# MCU.net
KiCad netlist of a schematic drawn in Altium Designer
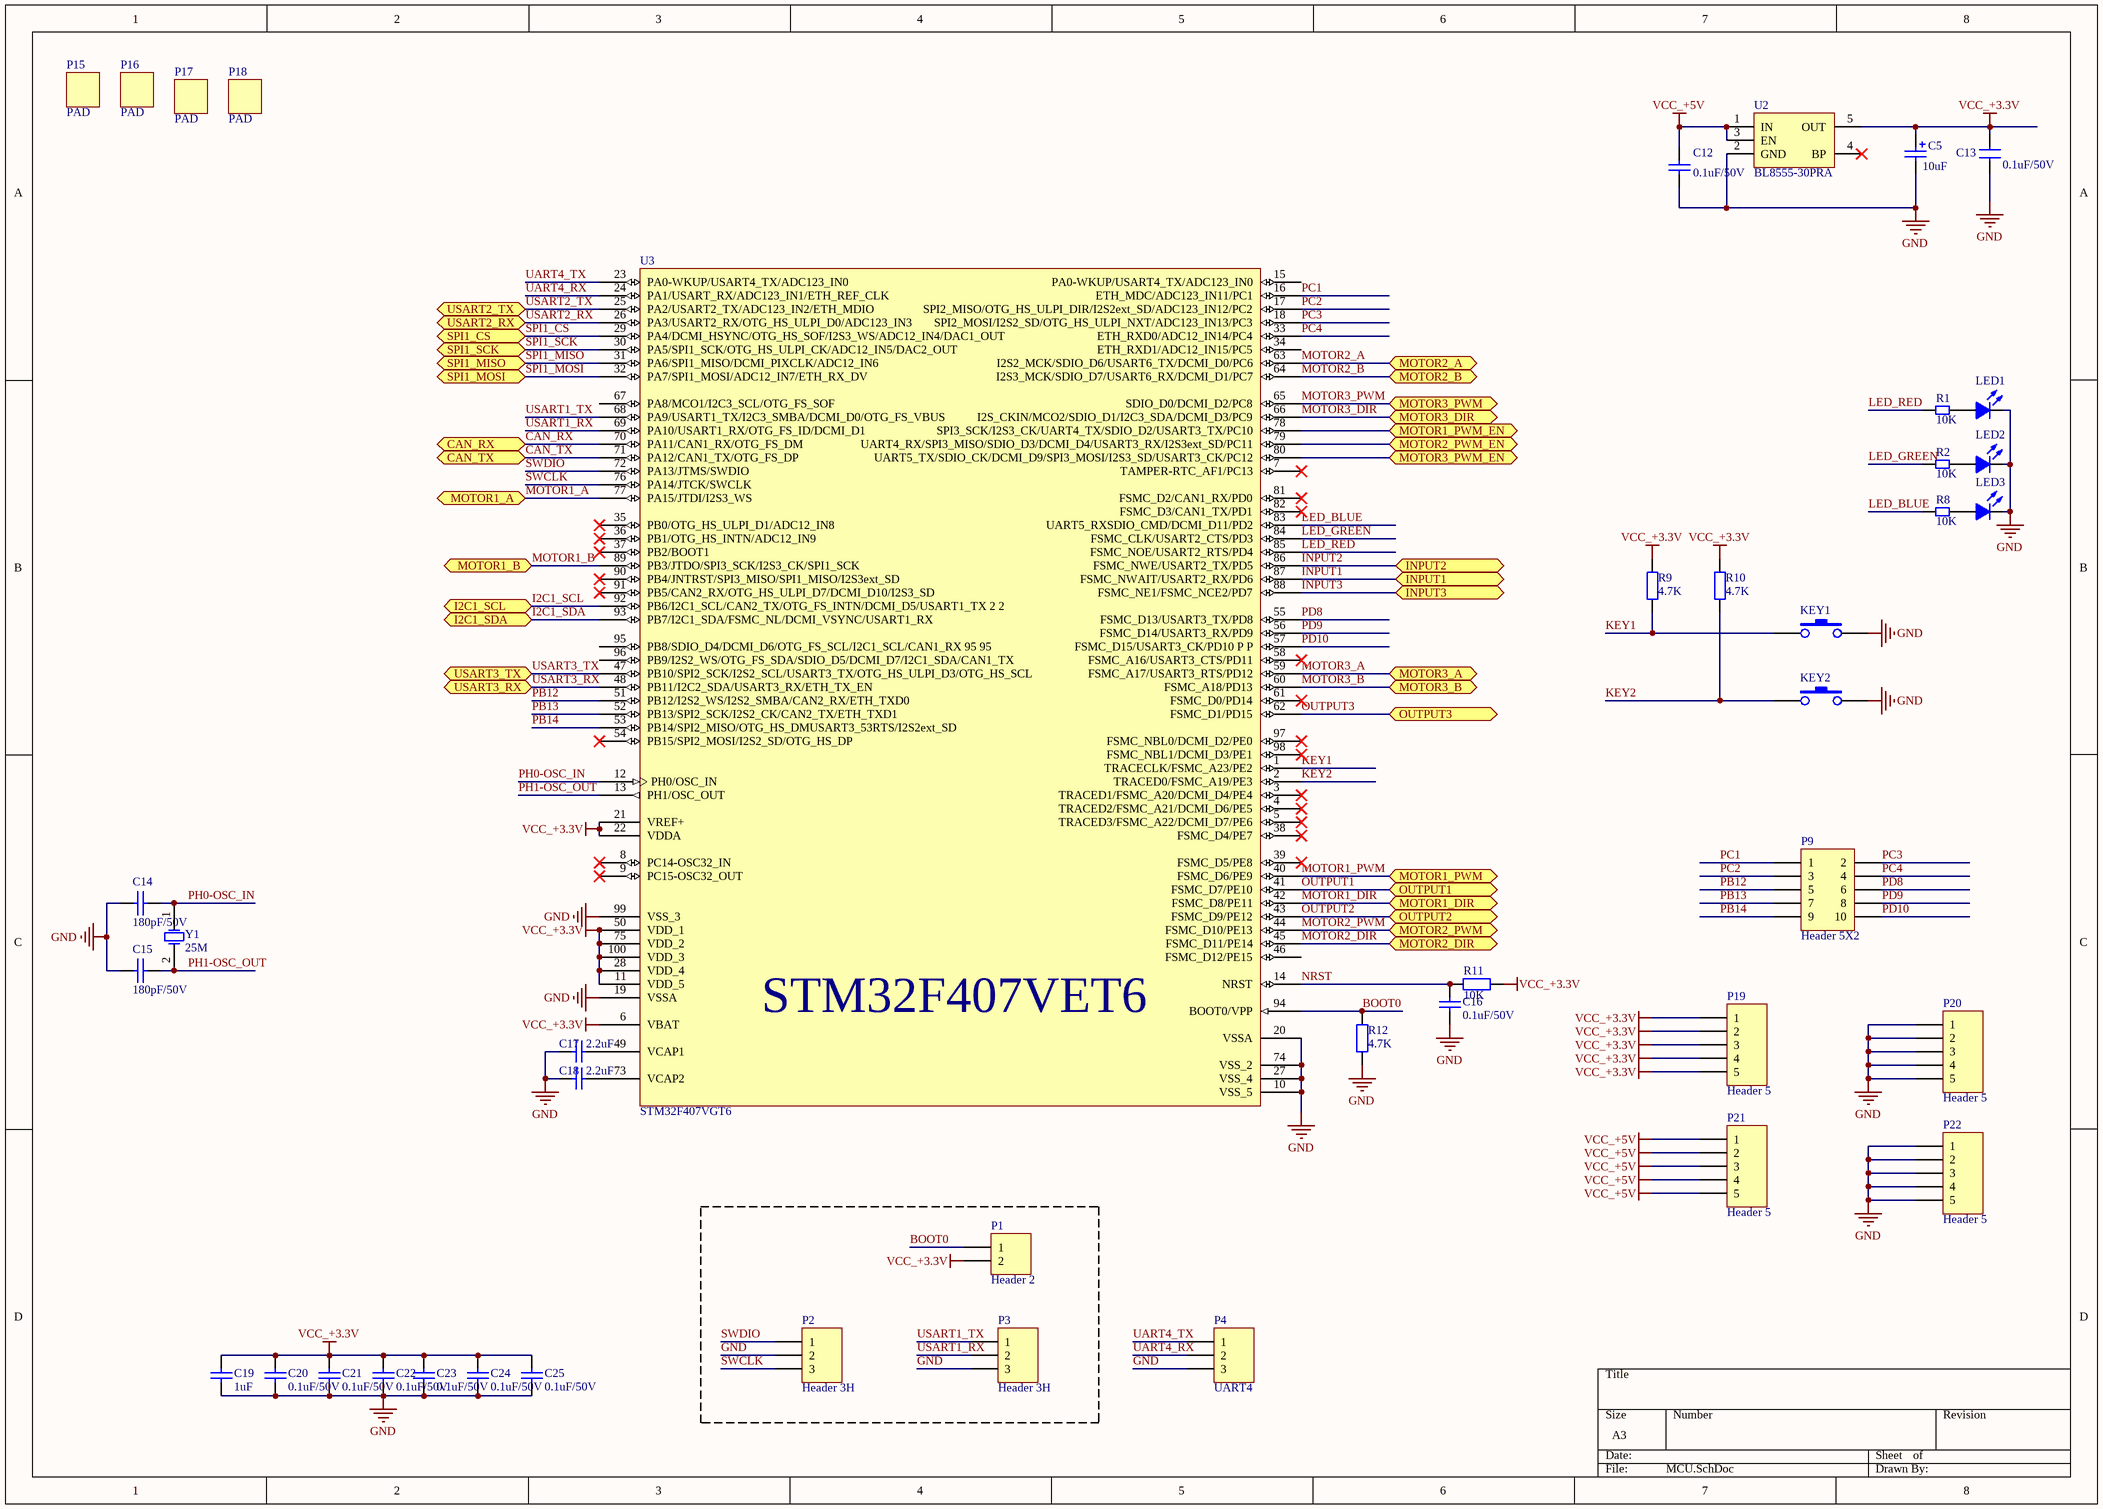
[diagram p0: MCU.SchDoc]

(export (version "E")
  (design (tool "Eeschema 10.0.6"))
  (components
    (comp (ref "C5")
      (value "10uF")
      (footprint "CAPTANC")
      (description "Polarized Capacitor (Radial)")
      (fields (field (name "PUBLISHER") "Altium Limited"))
      (libsource (lib "Calf") (part "Cap Pol"))
    )
    (comp (ref "C12")
      (value "0.1uF/50V")
      (footprint "0603C")
      (description "Capacitor")
      (fields (field (name "PUBLISHER") "Altium Limited"))
      (libsource (lib "Calf") (part "Cap"))
    )
    (comp (ref "C13") (value "0.1uF/50V") (footprint "0603C") (libsource (lib "0603C") (part "CAP")))
    (comp (ref "C14") (value "180pF/50V") (footprint "0603C") (libsource (lib "*") (part "0603C")))
    (comp (ref "C15") (value "180pF/50V") (footprint "0603C") (libsource (lib "*") (part "0603C")))
    (comp (ref "C16")
      (value "0.1uF/50V")
      (footprint "0603C")
      (description "Capacitor")
      (fields (field (name "PUBLISHER") "Altium Limited"))
      (libsource (lib "Calf") (part "Cap"))
    )
    (comp (ref "C17")
      (value "2.2uF")
      (footprint "0603C")
      (description "Capacitor")
      (fields (field (name "PUBLISHER") "Altium Limited"))
      (libsource (lib "Calf") (part "Cap"))
    )
    (comp (ref "C18")
      (value "2.2uF")
      (footprint "0603C")
      (description "Capacitor")
      (fields (field (name "PUBLISHER") "Altium Limited"))
      (libsource (lib "Calf") (part "Cap"))
    )
    (comp (ref "C19")
      (value "1uF")
      (footprint "0603C")
      (description "Capacitor")
      (fields (field (name "PUBLISHER") "Altium Limited"))
      (libsource (lib "Calf") (part "Cap"))
    )
    (comp (ref "C20")
      (value "0.1uF/50V")
      (footprint "0603C")
      (description "Capacitor")
      (fields (field (name "PUBLISHER") "Altium Limited"))
      (libsource (lib "Calf") (part "Cap"))
    )
    (comp (ref "C21")
      (value "0.1uF/50V")
      (footprint "0603C")
      (description "Capacitor")
      (fields (field (name "PUBLISHER") "Altium Limited"))
      (libsource (lib "Calf") (part "Cap"))
    )
    (comp (ref "C22")
      (value "0.1uF/50V")
      (footprint "0603C")
      (description "Capacitor")
      (fields (field (name "PUBLISHER") "Altium Limited"))
      (libsource (lib "Calf") (part "Cap"))
    )
    (comp (ref "C23")
      (value "0.1uF/50V")
      (footprint "0603C")
      (description "Capacitor")
      (fields (field (name "PUBLISHER") "Altium Limited"))
      (libsource (lib "Calf") (part "Cap"))
    )
    (comp (ref "C24")
      (value "0.1uF/50V")
      (footprint "0603C")
      (description "Capacitor")
      (fields (field (name "PUBLISHER") "Altium Limited"))
      (libsource (lib "Calf") (part "Cap"))
    )
    (comp (ref "C25")
      (value "0.1uF/50V")
      (footprint "0603C")
      (description "Capacitor")
      (fields (field (name "PUBLISHER") "Altium Limited"))
      (libsource (lib "Calf") (part "Cap"))
    )
    (comp (ref "KEY1") (value "~") (footprint "KEY_SMT") (libsource (lib "stmDL") (part "SW-PB")))
    (comp (ref "KEY2") (value "~") (footprint "KEY_SMT") (libsource (lib "stmDL") (part "SW-PB")))
    (comp (ref "LED1")
      (value "LED")
      (footprint "LED-0603")
      (description "Typical INFRARED GaAs LED")
      (fields (field (name "PUBLISHER") "Altium Limited"))
      (libsource (lib "Calf") (part "LED"))
    )
    (comp (ref "LED2")
      (value "LED")
      (footprint "LED-0603")
      (description "Typical INFRARED GaAs LED")
      (fields (field (name "PUBLISHER") "Altium Limited"))
      (libsource (lib "Calf") (part "LED"))
    )
    (comp (ref "LED3")
      (value "LED")
      (footprint "LED-0603")
      (description "Typical INFRARED GaAs LED")
      (fields (field (name "PUBLISHER") "Altium Limited"))
      (libsource (lib "Calf") (part "LED"))
    )
    (comp (ref "P1")
      (value "Header 2")
      (footprint "HDR1*2")
      (description "Header, 2-Pin")
      (fields (field (name "PUBLISHER") "Altium Limited"))
      (libsource (lib "Miscellaneous Connectors") (part "Header 2"))
    )
    (comp (ref "P2")
      (value "Header 3H")
      (footprint "XH254-3P")
      (description "Header, 3-Pin, Right Angle")
      (fields (field (name "PUBLISHER") "Altium Limited"))
      (libsource (lib "Miscellaneous Connectors") (part "Header 3H"))
    )
    (comp (ref "P3")
      (value "Header 3H")
      (footprint "XH254-3P")
      (description "Header, 3-Pin, Right Angle")
      (fields (field (name "PUBLISHER") "Altium Limited"))
      (libsource (lib "Miscellaneous Connectors") (part "Header 3H"))
    )
    (comp (ref "P4")
      (value "UART4")
      (footprint "XH254-3P")
      (description "Header, 3-Pin, Right Angle")
      (fields (field (name "PUBLISHER") "Altium Limited"))
      (libsource (lib "Miscellaneous Connectors") (part "Header 3H"))
    )
    (comp (ref "P9")
      (value "Header 5X2")
      (footprint "HDR2X5")
      (description "Header, 5-Pin, Dual row")
      (fields (field (name "PUBLISHER") "Altium Limited"))
      (libsource (lib "Miscellaneous Connectors") (part "Header 5X2"))
    )
    (comp (ref "P15") (value "PAD") (footprint "PAD 3mm") (libsource (lib "Schlib") (part "PAD")))
    (comp (ref "P16") (value "PAD") (footprint "PAD 3mm") (libsource (lib "Schlib") (part "PAD")))
    (comp (ref "P17") (value "PAD") (footprint "PAD 3mm") (libsource (lib "Schlib") (part "PAD")))
    (comp (ref "P18") (value "PAD") (footprint "PAD 3mm") (libsource (lib "Schlib") (part "PAD")))
    (comp (ref "P19")
      (value "Header 5")
      (footprint "HDR1X5")
      (description "Header, 5-Pin")
      (fields (field (name "PUBLISHER") "Altium Limited"))
      (libsource (lib "Miscellaneous Connectors") (part "Header 5"))
    )
    (comp (ref "P20")
      (value "Header 5")
      (footprint "HDR1X5")
      (description "Header, 5-Pin")
      (fields (field (name "PUBLISHER") "Altium Limited"))
      (libsource (lib "Miscellaneous Connectors") (part "Header 5"))
    )
    (comp (ref "P21")
      (value "Header 5")
      (footprint "HDR1X5")
      (description "Header, 5-Pin")
      (fields (field (name "PUBLISHER") "Altium Limited"))
      (libsource (lib "Miscellaneous Connectors") (part "Header 5"))
    )
    (comp (ref "P22")
      (value "Header 5")
      (footprint "HDR1X5")
      (description "Header, 5-Pin")
      (fields (field (name "PUBLISHER") "Altium Limited"))
      (libsource (lib "Miscellaneous Connectors") (part "Header 5"))
    )
    (comp (ref "R1")
      (value "10K")
      (footprint "0603R")
      (description "Resistor")
      (fields (field (name "PUBLISHER") "Altium Limited"))
      (libsource (lib "Calf") (part "Res2"))
    )
    (comp (ref "R2")
      (value "10K")
      (footprint "0603R")
      (description "Resistor")
      (fields (field (name "PUBLISHER") "Altium Limited"))
      (libsource (lib "Calf") (part "Res2"))
    )
    (comp (ref "R8")
      (value "10K")
      (footprint "0603R")
      (description "Resistor")
      (fields (field (name "PUBLISHER") "Altium Limited"))
      (libsource (lib "Calf") (part "Res2"))
    )
    (comp (ref "R9") (value "4.7K") (footprint "0603R") (libsource (lib "*") (part "0603R")))
    (comp (ref "R10") (value "4.7K") (footprint "0603R") (libsource (lib "*") (part "0603R")))
    (comp (ref "R11") (value "10K") (footprint "0603R") (libsource (lib "") (part "0603R_2")))
    (comp (ref "R12") (value "4.7K") (footprint "0603R") (libsource (lib "") (part "0603R_1")))
    (comp (ref "U2") (value "BL8555-30PRA") (footprint "SOT23-5") (libsource (lib "Calf") (part "SGM2019")))
    (comp (ref "U3")
      (value "STM32F407VGT6")
      (footprint "LQFP-100_14x14x05P")
      (libsource (lib "STM32F407VGT6") (part "STM32F407VGT6"))
    )
    (comp (ref "Y1")
      (value "25M")
      (footprint "XTAL")
      (description "Crystal Oscillator")
      (fields (field (name "PUBLISHER") "Altium Limited"))
      (libsource (lib "*") (part "XTAL"))
    )
  )
  (nets
    (net (code "1") (name "/BOOT0") (class "Default")
      (node (ref "P1") (pin "1") (pinfunction "1_1") (pintype "passive"))
      (node (ref "R12") (pin "2") (pinfunction "2_2") (pintype "passive"))
      (node (ref "U3") (pin "94") (pinfunction "BOOT0/VPP_94") (pintype "input"))
    )
    (net (code "2") (name "/CAN_RX") (class "Default")
      (node (ref "U3") (pin "70") (pinfunction "PA11/CAN1_RX/OTG_FS_DM_70") (pintype "bidirectional"))
    )
    (net (code "3") (name "/CAN_TX") (class "Default")
      (node (ref "U3") (pin "71") (pinfunction "PA12/CAN1_TX/OTG_FS_DP_71") (pintype "bidirectional"))
    )
    (net (code "4") (name "/I2C1_SCL") (class "Default")
      (node (ref "U3") (pin "92") (pinfunction "PB6/I2C1_SCL/CAN2_TX/OTG_FS_INTN/DCMI_D5/USART1_TX_2_2_92") (pintype "bidirectional"))
    )
    (net (code "5") (name "/I2C1_SDA") (class "Default")
      (node (ref "U3") (pin "93") (pinfunction "PB7/I2C1_SDA/FSMC_NL/DCMI_VSYNC/USART1_RX_93") (pintype "bidirectional"))
    )
    (net (code "6") (name "/INPUT1") (class "Default")
      (node (ref "U3") (pin "87") (pinfunction "FSMC_NWAIT/USART2_RX/PD6_87") (pintype "bidirectional"))
    )
    (net (code "7") (name "/INPUT2") (class "Default")
      (node (ref "U3") (pin "86") (pinfunction "FSMC_NWE/USART2_TX/PD5_86") (pintype "bidirectional"))
    )
    (net (code "8") (name "/INPUT3") (class "Default")
      (node (ref "U3") (pin "88") (pinfunction "FSMC_NE1/FSMC_NCE2/PD7_88") (pintype "bidirectional"))
    )
    (net (code "9") (name "/KEY1") (class "Default")
      (node (ref "KEY1") (pin "1") (pinfunction "1_1") (pintype "passive"))
      (node (ref "R9") (pin "2") (pinfunction "2_2") (pintype "passive"))
      (node (ref "U3") (pin "1") (pinfunction "TRACECLK/FSMC_A23/PE2_1") (pintype "bidirectional"))
    )
    (net (code "10") (name "/KEY2") (class "Default")
      (node (ref "KEY2") (pin "1") (pinfunction "1_1") (pintype "passive"))
      (node (ref "R10") (pin "2") (pinfunction "2_2") (pintype "passive"))
      (node (ref "U3") (pin "2") (pinfunction "TRACED0/FSMC_A19/PE3_2") (pintype "bidirectional"))
    )
    (net (code "11") (name "/LED_BLUE") (class "Default")
      (node (ref "R8") (pin "1") (pinfunction "1_1") (pintype "passive"))
      (node (ref "U3") (pin "83") (pinfunction "UART5_RXSDIO_CMD/DCMI_D11/PD2_83") (pintype "bidirectional"))
    )
    (net (code "12") (name "/LED_GREEN") (class "Default")
      (node (ref "R2") (pin "1") (pinfunction "1_1") (pintype "passive"))
      (node (ref "U3") (pin "84") (pinfunction "FSMC_CLK/USART2_CTS/PD3_84") (pintype "bidirectional"))
    )
    (net (code "13") (name "/LED_RED") (class "Default")
      (node (ref "R1") (pin "1") (pinfunction "1_1") (pintype "passive"))
      (node (ref "U3") (pin "85") (pinfunction "FSMC_NOE/USART2_RTS/PD4_85") (pintype "bidirectional"))
    )
    (net (code "14") (name "/MOTOR1_A") (class "Default")
      (node (ref "U3") (pin "77") (pinfunction "PA15/JTDI/I2S3_WS_77") (pintype "bidirectional"))
    )
    (net (code "15") (name "/MOTOR1_B") (class "Default")
      (node (ref "U3") (pin "89") (pinfunction "PB3/JTDO/SPI3_SCK/I2S3_CK/SPI1_SCK_89") (pintype "bidirectional"))
    )
    (net (code "16") (name "/MOTOR1_DIR") (class "Default")
      (node (ref "U3") (pin "42") (pinfunction "FSMC_D8/PE11_42") (pintype "bidirectional"))
    )
    (net (code "17") (name "/MOTOR1_PWM") (class "Default")
      (node (ref "U3") (pin "40") (pinfunction "FSMC_D6/PE9_40") (pintype "bidirectional"))
    )
    (net (code "18") (name "/MOTOR1_PWM_EN") (class "Default")
      (node (ref "U3") (pin "78") (pinfunction "SPI3_SCK/I2S3_CK/UART4_TX/SDIO_D2/USART3_TX/PC10_78") (pintype "bidirectional"))
    )
    (net (code "19") (name "/MOTOR2_A") (class "Default")
      (node (ref "U3") (pin "63") (pinfunction "I2S2_MCK/SDIO_D6/USART6_TX/DCMI_D0/PC6_63") (pintype "bidirectional"))
    )
    (net (code "20") (name "/MOTOR2_B") (class "Default")
      (node (ref "U3") (pin "64") (pinfunction "I2S3_MCK/SDIO_D7/USART6_RX/DCMI_D1/PC7_64") (pintype "bidirectional"))
    )
    (net (code "21") (name "/MOTOR2_DIR") (class "Default")
      (node (ref "U3") (pin "45") (pinfunction "FSMC_D11/PE14_45") (pintype "bidirectional"))
    )
    (net (code "22") (name "/MOTOR2_PWM") (class "Default")
      (node (ref "U3") (pin "44") (pinfunction "FSMC_D10/PE13_44") (pintype "bidirectional"))
    )
    (net (code "23") (name "/MOTOR2_PWM_EN") (class "Default")
      (node (ref "U3") (pin "79") (pinfunction "UART4_RX/SPI3_MISO/SDIO_D3/DCMI_D4/USART3_RX/I2S3ext_SD/PC11_79") (pintype "bidirectional"))
    )
    (net (code "24") (name "/MOTOR3_A") (class "Default")
      (node (ref "U3") (pin "59") (pinfunction "FSMC_A17/USART3_RTS/PD12_59") (pintype "bidirectional"))
    )
    (net (code "25") (name "/MOTOR3_B") (class "Default")
      (node (ref "U3") (pin "60") (pinfunction "FSMC_A18/PD13_60") (pintype "bidirectional"))
    )
    (net (code "26") (name "/MOTOR3_DIR") (class "Default")
      (node (ref "U3") (pin "66") (pinfunction "I2S_CKIN/MCO2/SDIO_D1/I2C3_SDA/DCMI_D3/PC9_66") (pintype "bidirectional"))
    )
    (net (code "27") (name "/MOTOR3_PWM") (class "Default")
      (node (ref "U3") (pin "65") (pinfunction "SDIO_D0/DCMI_D2/PC8_65") (pintype "bidirectional"))
    )
    (net (code "28") (name "/MOTOR3_PWM_EN") (class "Default")
      (node (ref "U3") (pin "80") (pinfunction "UART5_TX/SDIO_CK/DCMI_D9/SPI3_MOSI/I2S3_SD/USART3_CK/PC12_80") (pintype "bidirectional"))
    )
    (net (code "29") (name "/NRST") (class "Default")
      (node (ref "C16") (pin "2") (pinfunction "2_2") (pintype "passive"))
      (node (ref "R11") (pin "2") (pinfunction "2_2") (pintype "passive"))
      (node (ref "U3") (pin "14") (pinfunction "NRST_14") (pintype "bidirectional"))
    )
    (net (code "30") (name "/OUTPUT1") (class "Default")
      (node (ref "U3") (pin "41") (pinfunction "FSMC_D7/PE10_41") (pintype "bidirectional"))
    )
    (net (code "31") (name "/OUTPUT2") (class "Default")
      (node (ref "U3") (pin "43") (pinfunction "FSMC_D9/PE12_43") (pintype "bidirectional"))
    )
    (net (code "32") (name "/OUTPUT3") (class "Default")
      (node (ref "U3") (pin "62") (pinfunction "FSMC_D1/PD15_62") (pintype "bidirectional"))
    )
    (net (code "33") (name "/PB12") (class "Default")
      (node (ref "P9") (pin "5") (pinfunction "5_5") (pintype "passive"))
      (node (ref "U3") (pin "51") (pinfunction "PB12/I2S2_WS/I2S2_SMBA/CAN2_RX/ETH_TXD0_51") (pintype "bidirectional"))
    )
    (net (code "34") (name "/PB13") (class "Default")
      (node (ref "P9") (pin "7") (pinfunction "7_7") (pintype "passive"))
      (node (ref "U3") (pin "52") (pinfunction "PB13/SPI2_SCK/I2S2_CK/CAN2_TX/ETH_TXD1_52") (pintype "bidirectional"))
    )
    (net (code "35") (name "/PB14") (class "Default")
      (node (ref "P9") (pin "9") (pinfunction "9_9") (pintype "passive"))
      (node (ref "U3") (pin "53") (pinfunction "PB14/SPI2_MISO/OTG_HS_DMUSART3_53RTS/I2S2ext_SD_53") (pintype "bidirectional"))
    )
    (net (code "36") (name "/PC1") (class "Default")
      (node (ref "P9") (pin "1") (pinfunction "1_1") (pintype "passive"))
      (node (ref "U3") (pin "16") (pinfunction "ETH_MDC/ADC123_IN11/PC1_16") (pintype "bidirectional"))
    )
    (net (code "37") (name "/PC2") (class "Default")
      (node (ref "P9") (pin "3") (pinfunction "3_3") (pintype "passive"))
      (node (ref "U3") (pin "17") (pinfunction "SPI2_MISO/OTG_HS_ULPI_DIR/I2S2ext_SD/ADC123_IN12/PC2_17") (pintype "bidirectional"))
    )
    (net (code "38") (name "/PC3") (class "Default")
      (node (ref "P9") (pin "2") (pinfunction "2_2") (pintype "passive"))
      (node (ref "U3") (pin "18") (pinfunction "SPI2_MOSI/I2S2_SD/OTG_HS_ULPI_NXT/ADC123_IN13/PC3_18") (pintype "bidirectional"))
    )
    (net (code "39") (name "/PC4") (class "Default")
      (node (ref "P9") (pin "4") (pinfunction "4_4") (pintype "passive"))
      (node (ref "U3") (pin "33") (pinfunction "ETH_RXD0/ADC12_IN14/PC4_33") (pintype "bidirectional"))
    )
    (net (code "40") (name "/PD8") (class "Default")
      (node (ref "P9") (pin "6") (pinfunction "6_6") (pintype "passive"))
      (node (ref "U3") (pin "55") (pinfunction "FSMC_D13/USART3_TX/PD8_55") (pintype "bidirectional"))
    )
    (net (code "41") (name "/PD9") (class "Default")
      (node (ref "P9") (pin "8") (pinfunction "8_8") (pintype "passive"))
      (node (ref "U3") (pin "56") (pinfunction "FSMC_D14/USART3_RX/PD9_56") (pintype "bidirectional"))
    )
    (net (code "42") (name "/PD10") (class "Default")
      (node (ref "P9") (pin "10") (pinfunction "10_10") (pintype "passive"))
      (node (ref "U3") (pin "57") (pinfunction "FSMC_D15/USART3_CK/PD10_P_P_57") (pintype "bidirectional"))
    )
    (net (code "43") (name "/PH0-OSC_IN") (class "Default")
      (node (ref "C14") (pin "2") (pintype "passive"))
      (node (ref "U3") (pin "12") (pinfunction "PH0/OSC_IN_12") (pintype "input"))
      (node (ref "Y1") (pin "1") (pinfunction "OSC1_1") (pintype "passive"))
    )
    (net (code "44") (name "/PH1-OSC_OUT") (class "Default")
      (node (ref "C15") (pin "2") (pintype "passive"))
      (node (ref "U3") (pin "13") (pinfunction "PH1/OSC_OUT_13") (pintype "output"))
      (node (ref "Y1") (pin "2") (pinfunction "OSC2_2") (pintype "passive"))
    )
    (net (code "45") (name "/SPI1_CS") (class "Default")
      (node (ref "U3") (pin "29") (pinfunction "PA4/DCMI_HSYNC/OTG_HS_SOF/I2S3_WS/ADC12_IN4/DAC1_OUT_29") (pintype "bidirectional"))
    )
    (net (code "46") (name "/SPI1_MISO") (class "Default")
      (node (ref "U3") (pin "31") (pinfunction "PA6/SPI1_MISO/DCMI_PIXCLK/ADC12_IN6_31") (pintype "bidirectional"))
    )
    (net (code "47") (name "/SPI1_MOSI") (class "Default")
      (node (ref "U3") (pin "32") (pinfunction "PA7/SPI1_MOSI/ADC12_IN7/ETH_RX_DV_32") (pintype "bidirectional"))
    )
    (net (code "48") (name "/SPI1_SCK") (class "Default")
      (node (ref "U3") (pin "30") (pinfunction "PA5/SPI1_SCK/OTG_HS_ULPI_CK/ADC12_IN5/DAC2_OUT_30") (pintype "bidirectional"))
    )
    (net (code "49") (name "/SWCLK") (class "Default")
      (node (ref "P2") (pin "3") (pinfunction "3_3") (pintype "passive"))
      (node (ref "U3") (pin "76") (pinfunction "PA14/JTCK/SWCLK_76") (pintype "bidirectional"))
    )
    (net (code "50") (name "/SWDIO") (class "Default")
      (node (ref "P2") (pin "1") (pinfunction "1_1") (pintype "passive"))
      (node (ref "U3") (pin "72") (pinfunction "PA13/JTMS/SWDIO_72") (pintype "bidirectional"))
    )
    (net (code "51") (name "/UART4_RX") (class "Default")
      (node (ref "P4") (pin "2") (pinfunction "2_2") (pintype "passive"))
      (node (ref "U3") (pin "24") (pinfunction "PA1/USART_RX/ADC123_IN1/ETH_REF_CLK_24") (pintype "bidirectional"))
    )
    (net (code "52") (name "/UART4_TX") (class "Default")
      (node (ref "P4") (pin "1") (pinfunction "1_1") (pintype "passive"))
      (node (ref "U3") (pin "23") (pinfunction "PA0-WKUP/USART4_TX/ADC123_IN0_23") (pintype "bidirectional"))
    )
    (net (code "53") (name "/USART1_RX") (class "Default")
      (node (ref "P3") (pin "2") (pinfunction "2_2") (pintype "passive"))
      (node (ref "U3") (pin "69") (pinfunction "PA10/USART1_RX/OTG_FS_ID/DCMI_D1_69") (pintype "bidirectional"))
    )
    (net (code "54") (name "/USART1_TX") (class "Default")
      (node (ref "P3") (pin "1") (pinfunction "1_1") (pintype "passive"))
      (node (ref "U3") (pin "68") (pinfunction "PA9/USART1_TX/I2C3_SMBA/DCMI_D0/OTG_FS_VBUS_68") (pintype "bidirectional"))
    )
    (net (code "55") (name "/USART2_RX") (class "Default")
      (node (ref "U3") (pin "26") (pinfunction "PA3/USART2_RX/OTG_HS_ULPI_D0/ADC123_IN3_26") (pintype "bidirectional"))
    )
    (net (code "56") (name "/USART2_TX") (class "Default")
      (node (ref "U3") (pin "25") (pinfunction "PA2/USART2_TX/ADC123_IN2/ETH_MDIO_25") (pintype "bidirectional"))
    )
    (net (code "57") (name "/USART3_RX") (class "Default")
      (node (ref "U3") (pin "48") (pinfunction "PB11/I2C2_SDA/USART3_RX/ETH_TX_EN_48") (pintype "bidirectional"))
    )
    (net (code "58") (name "/USART3_TX") (class "Default")
      (node (ref "U3") (pin "47") (pinfunction "PB10/SPI2_SCK/I2S2_SCL/USART3_TX/OTG_HS_ULPI_D3/OTG_HS_SCL_47") (pintype "bidirectional"))
    )
    (net (code "59") (name "GND") (class "Default")
      (node (ref "C12") (pin "1") (pinfunction "1_1") (pintype "passive"))
      (node (ref "C13") (pin "2") (pinfunction "2_2") (pintype "passive"))
      (node (ref "C14") (pin "1") (pintype "passive"))
      (node (ref "C15") (pin "1") (pintype "passive"))
      (node (ref "C16") (pin "1") (pinfunction "1_1") (pintype "passive"))
      (node (ref "C17") (pin "2") (pinfunction "2_2") (pintype "passive"))
      (node (ref "C18") (pin "2") (pinfunction "2_2") (pintype "passive"))
      (node (ref "C19") (pin "1") (pinfunction "1_1") (pintype "passive"))
      (node (ref "C20") (pin "1") (pinfunction "1_1") (pintype "passive"))
      (node (ref "C21") (pin "1") (pinfunction "1_1") (pintype "passive"))
      (node (ref "C22") (pin "1") (pinfunction "1_1") (pintype "passive"))
      (node (ref "C23") (pin "1") (pinfunction "1_1") (pintype "passive"))
      (node (ref "C24") (pin "1") (pinfunction "1_1") (pintype "passive"))
      (node (ref "C25") (pin "1") (pinfunction "1_1") (pintype "passive"))
      (node (ref "C5") (pin "2") (pinfunction "2_2") (pintype "passive"))
      (node (ref "KEY1") (pin "2") (pinfunction "2_2") (pintype "passive"))
      (node (ref "KEY2") (pin "2") (pinfunction "2_2") (pintype "passive"))
      (node (ref "LED1") (pin "2") (pinfunction "K_2") (pintype "passive"))
      (node (ref "LED2") (pin "2") (pinfunction "K_2") (pintype "passive"))
      (node (ref "LED3") (pin "2") (pinfunction "K_2") (pintype "passive"))
      (node (ref "P2") (pin "2") (pinfunction "2_2") (pintype "passive"))
      (node (ref "P20") (pin "1") (pinfunction "1_1") (pintype "passive"))
      (node (ref "P20") (pin "2") (pinfunction "2_2") (pintype "passive"))
      (node (ref "P20") (pin "3") (pinfunction "3_3") (pintype "passive"))
      (node (ref "P20") (pin "4") (pinfunction "4_4") (pintype "passive"))
      (node (ref "P20") (pin "5") (pinfunction "5_5") (pintype "passive"))
      (node (ref "P22") (pin "1") (pinfunction "1_1") (pintype "passive"))
      (node (ref "P22") (pin "2") (pinfunction "2_2") (pintype "passive"))
      (node (ref "P22") (pin "3") (pinfunction "3_3") (pintype "passive"))
      (node (ref "P22") (pin "4") (pinfunction "4_4") (pintype "passive"))
      (node (ref "P22") (pin "5") (pinfunction "5_5") (pintype "passive"))
      (node (ref "P3") (pin "3") (pinfunction "3_3") (pintype "passive"))
      (node (ref "P4") (pin "3") (pinfunction "3_3") (pintype "passive"))
      (node (ref "R12") (pin "1") (pinfunction "1_1") (pintype "passive"))
      (node (ref "U2") (pin "2") (pinfunction "GND_2") (pintype "passive"))
      (node (ref "U3") (pin "10") (pinfunction "VSS_5_10") (pintype "power_in"))
      (node (ref "U3") (pin "19") (pinfunction "VSSA_19") (pintype "power_in"))
      (node (ref "U3") (pin "20") (pinfunction "VSSA_20") (pintype "power_in"))
      (node (ref "U3") (pin "27") (pinfunction "VSS_4_27") (pintype "power_in"))
      (node (ref "U3") (pin "74") (pinfunction "VSS_2_74") (pintype "power_in"))
      (node (ref "U3") (pin "99") (pinfunction "VSS_3_99") (pintype "power_in"))
    )
    (net (code "60") (name "Net-(LED1-A)") (class "Default")
      (node (ref "LED1") (pin "1") (pinfunction "A_1") (pintype "passive"))
      (node (ref "R1") (pin "2") (pinfunction "2_2") (pintype "passive"))
    )
    (net (code "61") (name "Net-(LED2-A)") (class "Default")
      (node (ref "LED2") (pin "1") (pinfunction "A_1") (pintype "passive"))
      (node (ref "R2") (pin "2") (pinfunction "2_2") (pintype "passive"))
    )
    (net (code "62") (name "Net-(LED3-A)") (class "Default")
      (node (ref "LED3") (pin "1") (pinfunction "A_1") (pintype "passive"))
      (node (ref "R8") (pin "2") (pinfunction "2_2") (pintype "passive"))
    )
    (net (code "63") (name "Net-(U3-VCAP1)") (class "Default")
      (node (ref "C17") (pin "1") (pinfunction "1_1") (pintype "passive"))
      (node (ref "U3") (pin "49") (pinfunction "VCAP1_49") (pintype "power_in"))
    )
    (net (code "64") (name "Net-(U3-VCAP2)") (class "Default")
      (node (ref "C18") (pin "1") (pinfunction "1_1") (pintype "passive"))
      (node (ref "U3") (pin "73") (pinfunction "VCAP2_73") (pintype "passive"))
    )
    (net (code "65") (name "VCC_+3.3V") (class "Default")
      (node (ref "C13") (pin "1") (pinfunction "1_1") (pintype "passive"))
      (node (ref "C19") (pin "2") (pinfunction "2_2") (pintype "passive"))
      (node (ref "C20") (pin "2") (pinfunction "2_2") (pintype "passive"))
      (node (ref "C21") (pin "2") (pinfunction "2_2") (pintype "passive"))
      (node (ref "C22") (pin "2") (pinfunction "2_2") (pintype "passive"))
      (node (ref "C23") (pin "2") (pinfunction "2_2") (pintype "passive"))
      (node (ref "C24") (pin "2") (pinfunction "2_2") (pintype "passive"))
      (node (ref "C25") (pin "2") (pinfunction "2_2") (pintype "passive"))
      (node (ref "C5") (pin "1") (pinfunction "1_1") (pintype "passive"))
      (node (ref "P1") (pin "2") (pinfunction "2_2") (pintype "passive"))
      (node (ref "P19") (pin "1") (pinfunction "1_1") (pintype "passive"))
      (node (ref "P19") (pin "2") (pinfunction "2_2") (pintype "passive"))
      (node (ref "P19") (pin "3") (pinfunction "3_3") (pintype "passive"))
      (node (ref "P19") (pin "4") (pinfunction "4_4") (pintype "passive"))
      (node (ref "P19") (pin "5") (pinfunction "5_5") (pintype "passive"))
      (node (ref "R10") (pin "1") (pinfunction "1_1") (pintype "passive"))
      (node (ref "R11") (pin "1") (pinfunction "1_1") (pintype "passive"))
      (node (ref "R9") (pin "1") (pinfunction "1_1") (pintype "passive"))
      (node (ref "U2") (pin "5") (pinfunction "OUT_5") (pintype "passive"))
      (node (ref "U3") (pin "100") (pinfunction "VDD_3_100") (pintype "power_in"))
      (node (ref "U3") (pin "11") (pinfunction "VDD_5_11") (pintype "power_in"))
      (node (ref "U3") (pin "21") (pinfunction "VREF+_21") (pintype "power_in"))
      (node (ref "U3") (pin "22") (pinfunction "VDDA_22") (pintype "power_in"))
      (node (ref "U3") (pin "28") (pinfunction "VDD_4_28") (pintype "power_in"))
      (node (ref "U3") (pin "50") (pinfunction "VDD_1_50") (pintype "power_in"))
      (node (ref "U3") (pin "6") (pinfunction "VBAT_6") (pintype "power_in"))
      (node (ref "U3") (pin "75") (pinfunction "VDD_2_75") (pintype "power_in"))
    )
    (net (code "66") (name "VCC_+5V") (class "Default")
      (node (ref "C12") (pin "2") (pinfunction "2_2") (pintype "passive"))
      (node (ref "P21") (pin "1") (pinfunction "1_1") (pintype "passive"))
      (node (ref "P21") (pin "2") (pinfunction "2_2") (pintype "passive"))
      (node (ref "P21") (pin "3") (pinfunction "3_3") (pintype "passive"))
      (node (ref "P21") (pin "4") (pinfunction "4_4") (pintype "passive"))
      (node (ref "P21") (pin "5") (pinfunction "5_5") (pintype "passive"))
      (node (ref "U2") (pin "1") (pinfunction "IN_1") (pintype "passive"))
      (node (ref "U2") (pin "3") (pinfunction "EN_3") (pintype "passive"))
    )
    (net (code "67") (name "unconnected-(U2-BP-Pad4)") (class "Default")
      (node (ref "U2") (pin "4") (pinfunction "BP_4") (pintype "passive+no_connect"))
    )
    (net (code "68") (name "unconnected-(U3-ETH_RXD1{slash}ADC12_IN15{slash}PC5-Pad34)") (class "Default")
      (node (ref "U3") (pin "34") (pinfunction "ETH_RXD1/ADC12_IN15/PC5_34") (pintype "bidirectional"))
    )
    (net (code "69") (name "unconnected-(U3-FSMC_A16{slash}USART3_CTS{slash}PD11-Pad58)") (class "Default")
      (node (ref "U3") (pin "58") (pinfunction "FSMC_A16/USART3_CTS/PD11_58") (pintype "bidirectional+no_connect"))
    )
    (net (code "70") (name "unconnected-(U3-FSMC_D0{slash}PD14-Pad61)") (class "Default")
      (node (ref "U3") (pin "61") (pinfunction "FSMC_D0/PD14_61") (pintype "bidirectional+no_connect"))
    )
    (net (code "71") (name "unconnected-(U3-FSMC_D2{slash}CAN1_RX{slash}PD0-Pad81)") (class "Default")
      (node (ref "U3") (pin "81") (pinfunction "FSMC_D2/CAN1_RX/PD0_81") (pintype "bidirectional+no_connect"))
    )
    (net (code "72") (name "unconnected-(U3-FSMC_D3{slash}CAN1_TX{slash}PD1-Pad82)") (class "Default")
      (node (ref "U3") (pin "82") (pinfunction "FSMC_D3/CAN1_TX/PD1_82") (pintype "bidirectional+no_connect"))
    )
    (net (code "73") (name "unconnected-(U3-FSMC_D4{slash}PE7-Pad38)") (class "Default")
      (node (ref "U3") (pin "38") (pinfunction "FSMC_D4/PE7_38") (pintype "bidirectional+no_connect"))
    )
    (net (code "74") (name "unconnected-(U3-FSMC_D5{slash}PE8-Pad39)") (class "Default")
      (node (ref "U3") (pin "39") (pinfunction "FSMC_D5/PE8_39") (pintype "bidirectional+no_connect"))
    )
    (net (code "75") (name "unconnected-(U3-FSMC_D12{slash}PE15-Pad46)") (class "Default")
      (node (ref "U3") (pin "46") (pinfunction "FSMC_D12/PE15_46") (pintype "bidirectional"))
    )
    (net (code "76") (name "unconnected-(U3-FSMC_NBL0{slash}DCMI_D2{slash}PE0-Pad97)") (class "Default")
      (node (ref "U3") (pin "97") (pinfunction "FSMC_NBL0/DCMI_D2/PE0_97") (pintype "bidirectional+no_connect"))
    )
    (net (code "77") (name "unconnected-(U3-FSMC_NBL1{slash}DCMI_D3{slash}PE1-Pad98)") (class "Default")
      (node (ref "U3") (pin "98") (pinfunction "FSMC_NBL1/DCMI_D3/PE1_98") (pintype "bidirectional+no_connect"))
    )
    (net (code "78") (name "unconnected-(U3-PA0-WKUP{slash}USART4_TX{slash}ADC123_IN0-Pad15)") (class "Default")
      (node (ref "U3") (pin "15") (pinfunction "PA0-WKUP/USART4_TX/ADC123_IN0_15") (pintype "bidirectional"))
    )
    (net (code "79") (name "unconnected-(U3-PA8{slash}MCO1{slash}I2C3_SCL{slash}OTG_FS_SOF-Pad67)") (class "Default")
      (node (ref "U3") (pin "67") (pinfunction "PA8/MCO1/I2C3_SCL/OTG_FS_SOF_67") (pintype "bidirectional"))
    )
    (net (code "80") (name "unconnected-(U3-PB0{slash}OTG_HS_ULPI_D1{slash}ADC12_IN8-Pad35)") (class "Default")
      (node (ref "U3") (pin "35") (pinfunction "PB0/OTG_HS_ULPI_D1/ADC12_IN8_35") (pintype "bidirectional+no_connect"))
    )
    (net (code "81") (name "unconnected-(U3-PB1{slash}OTG_HS_INTN{slash}ADC12_IN9-Pad36)") (class "Default")
      (node (ref "U3") (pin "36") (pinfunction "PB1/OTG_HS_INTN/ADC12_IN9_36") (pintype "bidirectional+no_connect"))
    )
    (net (code "82") (name "unconnected-(U3-PB2{slash}BOOT1-Pad37)") (class "Default")
      (node (ref "U3") (pin "37") (pinfunction "PB2/BOOT1_37") (pintype "bidirectional+no_connect"))
    )
    (net (code "83") (name "unconnected-(U3-PB4{slash}JNTRST{slash}SPI3_MISO{slash}SPI1_MISO{slash}I2S3ext_SD-Pad90)") (class "Default")
      (node (ref "U3") (pin "90") (pinfunction "PB4/JNTRST/SPI3_MISO/SPI1_MISO/I2S3ext_SD_90") (pintype "bidirectional+no_connect"))
    )
    (net (code "84") (name "unconnected-(U3-PB5{slash}CAN2_RX{slash}OTG_HS_ULPI_D7{slash}DCMI_D10{slash}I2S3_SD-Pad91)") (class "Default")
      (node (ref "U3") (pin "91") (pinfunction "PB5/CAN2_RX/OTG_HS_ULPI_D7/DCMI_D10/I2S3_SD_91") (pintype "bidirectional+no_connect"))
    )
    (net (code "85") (name "unconnected-(U3-PB8{slash}SDIO_D4{slash}DCMI_D6{slash}OTG_FS_SCL{slash}I2C1_SCL{slash}CAN1_RX_95_95-Pad95)") (class "Default")
      (node (ref "U3") (pin "95") (pinfunction "PB8/SDIO_D4/DCMI_D6/OTG_FS_SCL/I2C1_SCL/CAN1_RX_95_95_95") (pintype "bidirectional"))
    )
    (net (code "86") (name "unconnected-(U3-PB9{slash}I2S2_WS{slash}OTG_FS_SDA{slash}SDIO_D5{slash}DCMI_D7{slash}I2C1_SDA{slash}CAN1_TX-Pad96)") (class "Default")
      (node (ref "U3") (pin "96") (pinfunction "PB9/I2S2_WS/OTG_FS_SDA/SDIO_D5/DCMI_D7/I2C1_SDA/CAN1_TX_96") (pintype "bidirectional"))
    )
    (net (code "87") (name "unconnected-(U3-PB15{slash}SPI2_MOSI{slash}I2S2_SD{slash}OTG_HS_DP-Pad54)") (class "Default")
      (node (ref "U3") (pin "54") (pinfunction "PB15/SPI2_MOSI/I2S2_SD/OTG_HS_DP_54") (pintype "bidirectional+no_connect"))
    )
    (net (code "88") (name "unconnected-(U3-PC14-OSC32_IN-Pad8)") (class "Default")
      (node (ref "U3") (pin "8") (pinfunction "PC14-OSC32_IN_8") (pintype "bidirectional+no_connect"))
    )
    (net (code "89") (name "unconnected-(U3-PC15-OSC32_OUT-Pad9)") (class "Default")
      (node (ref "U3") (pin "9") (pinfunction "PC15-OSC32_OUT_9") (pintype "bidirectional+no_connect"))
    )
    (net (code "90") (name "unconnected-(U3-TAMPER-RTC_AF1{slash}PC13-Pad7)") (class "Default")
      (node (ref "U3") (pin "7") (pinfunction "TAMPER-RTC_AF1/PC13_7") (pintype "bidirectional+no_connect"))
    )
    (net (code "91") (name "unconnected-(U3-TRACED1{slash}FSMC_A20{slash}DCMI_D4{slash}PE4-Pad3)") (class "Default")
      (node (ref "U3") (pin "3") (pinfunction "TRACED1/FSMC_A20/DCMI_D4/PE4_3") (pintype "bidirectional+no_connect"))
    )
    (net (code "92") (name "unconnected-(U3-TRACED2{slash}FSMC_A21{slash}DCMI_D6{slash}PE5-Pad4)") (class "Default")
      (node (ref "U3") (pin "4") (pinfunction "TRACED2/FSMC_A21/DCMI_D6/PE5_4") (pintype "bidirectional+no_connect"))
    )
    (net (code "93") (name "unconnected-(U3-TRACED3{slash}FSMC_A22{slash}DCMI_D7{slash}PE6-Pad5)") (class "Default")
      (node (ref "U3") (pin "5") (pinfunction "TRACED3/FSMC_A22/DCMI_D7/PE6_5") (pintype "bidirectional+no_connect"))
    )
  )
)
